# M452x2015.net
KiCad netlist of a schematic drawn in EAGLE
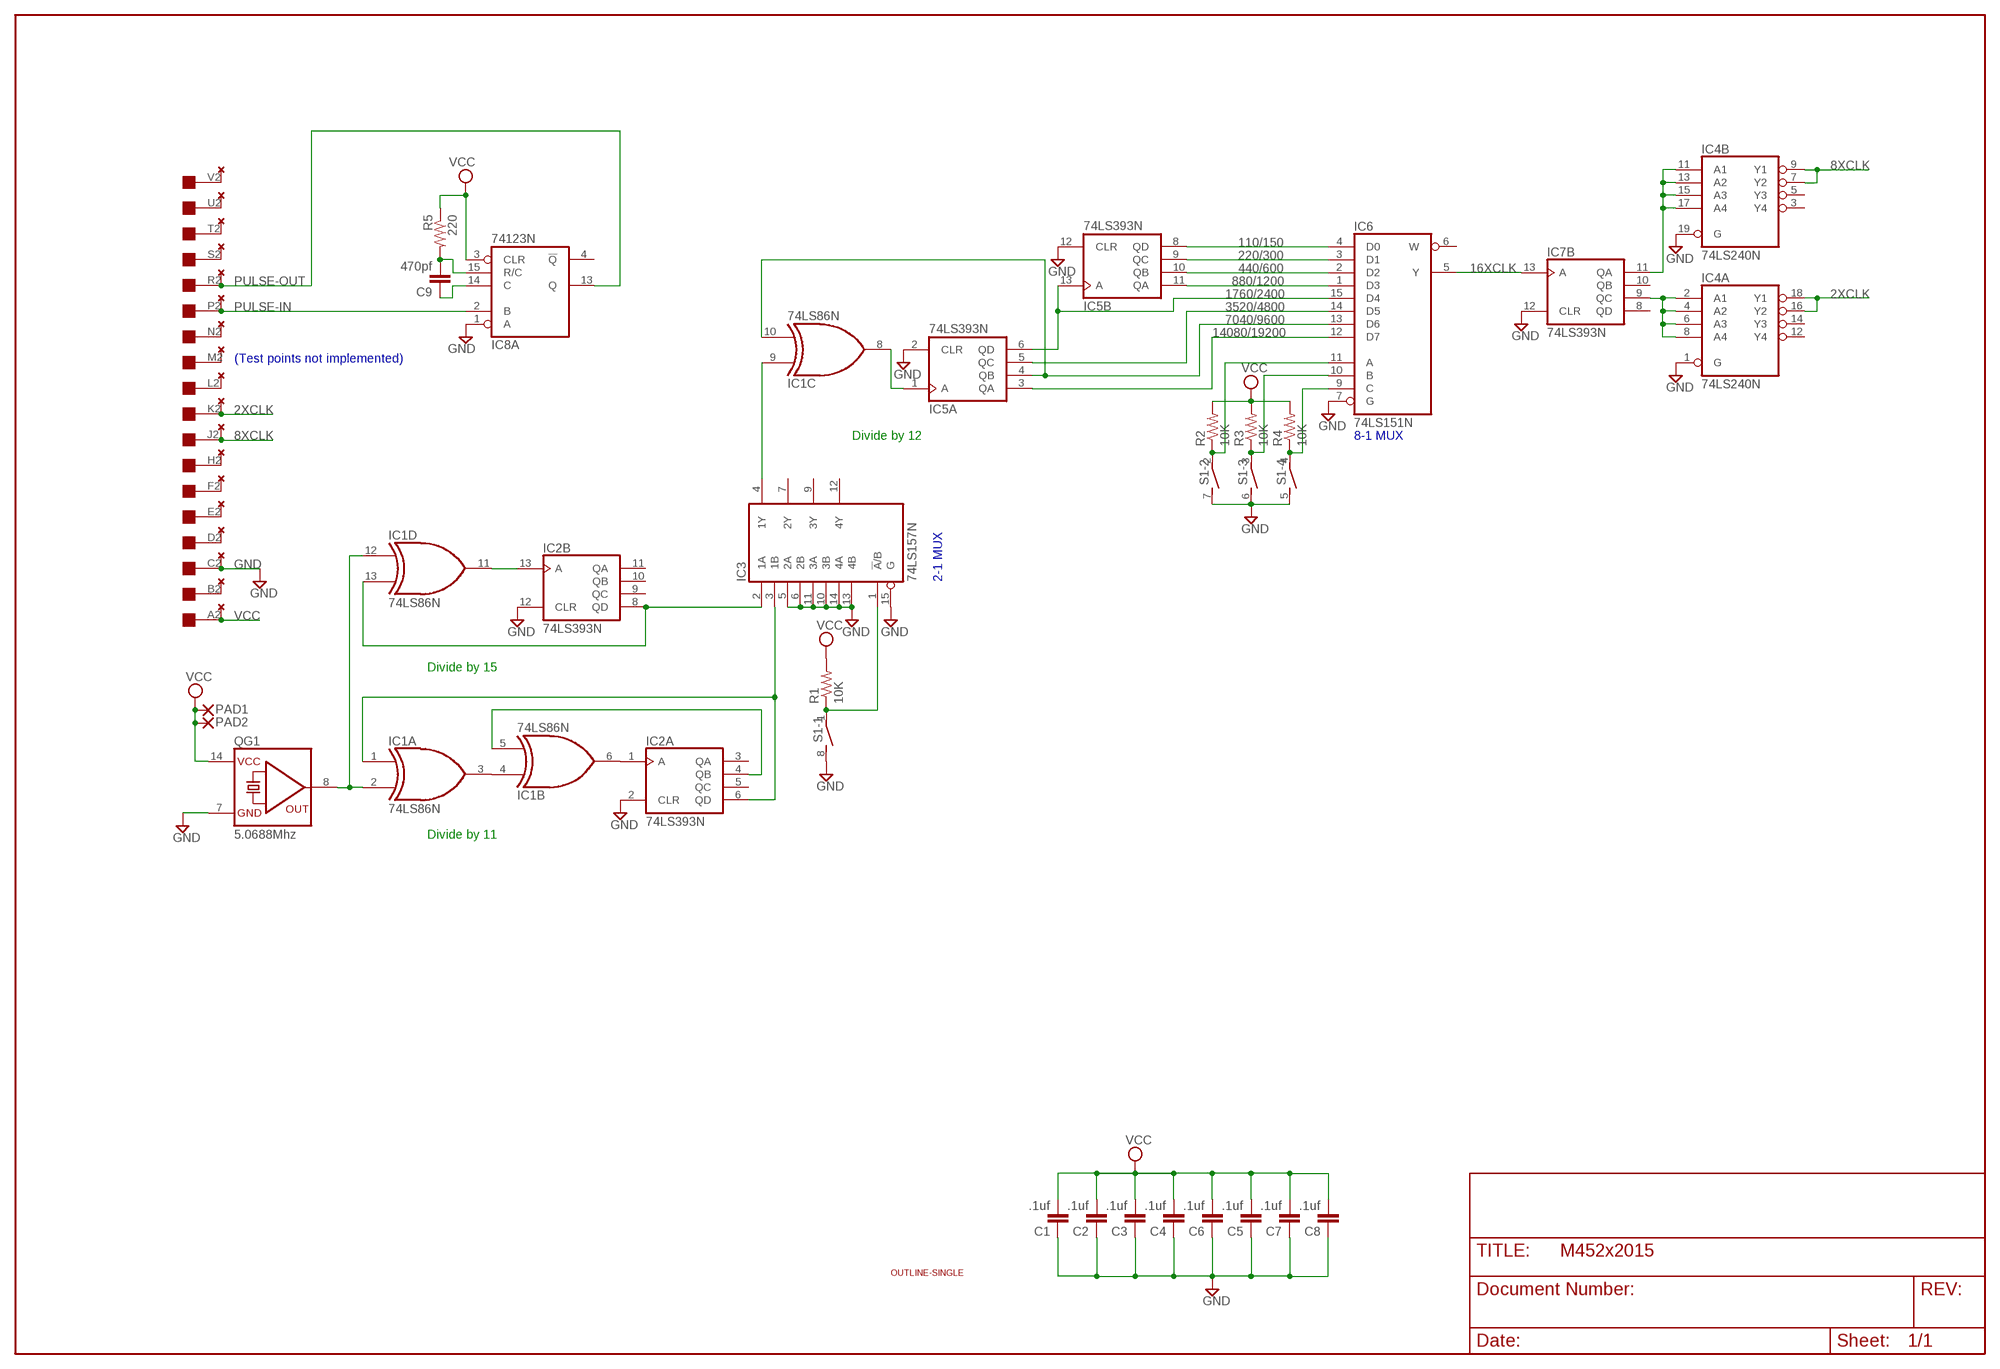
[diagram p0: schematic, sheet 1]

(export (version "E")
  (design (tool "Eeschema 10.0.6"))
  (components
    (comp (ref "C1")
      (value ".1uf")
      (footprint "eagle-import:C050-025X075")
      (libsource (lib "eagle-import") (part "C-EU050-025X075"))
    )
    (comp (ref "C2")
      (value ".1uf")
      (footprint "eagle-import:C050-025X075")
      (libsource (lib "eagle-import") (part "C-EU050-025X075"))
    )
    (comp (ref "C3")
      (value ".1uf")
      (footprint "eagle-import:C050-025X075")
      (libsource (lib "eagle-import") (part "C-EU050-025X075"))
    )
    (comp (ref "C4")
      (value ".1uf")
      (footprint "eagle-import:C050-025X075")
      (libsource (lib "eagle-import") (part "C-EU050-025X075"))
    )
    (comp (ref "C5")
      (value ".1uf")
      (footprint "eagle-import:C050-025X075")
      (libsource (lib "eagle-import") (part "C-EU050-025X075"))
    )
    (comp (ref "C6")
      (value ".1uf")
      (footprint "eagle-import:C050-025X075")
      (libsource (lib "eagle-import") (part "C-EU050-025X075"))
    )
    (comp (ref "C7")
      (value ".1uf")
      (footprint "eagle-import:C050-025X075")
      (libsource (lib "eagle-import") (part "C-EU050-025X075"))
    )
    (comp (ref "C8")
      (value ".1uf")
      (footprint "eagle-import:C050-025X075")
      (libsource (lib "eagle-import") (part "C-EU050-025X075"))
    )
    (comp (ref "C9")
      (value "470pf")
      (footprint "eagle-import:C050-025X075")
      (libsource (lib "eagle-import") (part "C-EU050-025X075"))
    )
    (comp (ref "IC1")
      (value "74LS86N")
      (footprint "eagle-import:DIL14")
      (libsource (lib "eagle-import") (part "7486NLS"))
    )
    (comp (ref "IC2")
      (value "74LS393N")
      (footprint "eagle-import:DIL14")
      (libsource (lib "eagle-import") (part "74393NLS"))
    )
    (comp (ref "IC3")
      (value "74LS157N")
      (footprint "eagle-import:DIL16")
      (libsource (lib "eagle-import") (part "74157NLS"))
    )
    (comp (ref "IC4")
      (value "74LS240N")
      (footprint "eagle-import:DIL20")
      (libsource (lib "eagle-import") (part "74240NLS"))
    )
    (comp (ref "IC5")
      (value "74LS393N")
      (footprint "eagle-import:DIL14")
      (libsource (lib "eagle-import") (part "74393NLS"))
    )
    (comp (ref "IC6")
      (value "74LS151N")
      (footprint "eagle-import:DIL16")
      (libsource (lib "eagle-import") (part "74151N"))
    )
    (comp (ref "IC7")
      (value "74LS393N")
      (footprint "eagle-import:DIL14")
      (libsource (lib "eagle-import") (part "74393NLS"))
    )
    (comp (ref "IC8")
      (value "74123N")
      (footprint "eagle-import:DIL16")
      (libsource (lib "eagle-import") (part "74123N"))
    )
    (comp (ref "PAD1")
      (value "1,6/0,8")
      (footprint "eagle-import:1,6_0,8")
      (libsource (lib "eagle-import") (part "1,6/0,8"))
    )
    (comp (ref "PAD2")
      (value "1,6/0,8")
      (footprint "eagle-import:1,6_0,8")
      (libsource (lib "eagle-import") (part "1,6/0,8"))
    )
    (comp (ref "QG1")
      (value "5.0688Mhz")
      (footprint "eagle-import:DIL14S")
      (libsource (lib "eagle-import") (part "QG5860"))
    )
    (comp (ref "R1")
      (value "10K")
      (footprint "eagle-import:0204_7")
      (libsource (lib "eagle-import") (part "R-US_0204/7"))
    )
    (comp (ref "R2")
      (value "10K")
      (footprint "eagle-import:0204_7")
      (libsource (lib "eagle-import") (part "R-US_0204/7"))
    )
    (comp (ref "R3")
      (value "10K")
      (footprint "eagle-import:0204_7")
      (libsource (lib "eagle-import") (part "R-US_0204/7"))
    )
    (comp (ref "R4")
      (value "10K")
      (footprint "eagle-import:0204_7")
      (libsource (lib "eagle-import") (part "R-US_0204/7"))
    )
    (comp (ref "R5")
      (value "220")
      (footprint "eagle-import:0204_7")
      (libsource (lib "eagle-import") (part "R-US_0204/7"))
    )
    (comp (ref "S1")
      (value "DIP04S")
      (footprint "eagle-import:DIP04S")
      (libsource (lib "eagle-import") (part "DIP04S"))
    )
    (comp (ref "U$1")
      (value "OUTLINE-SINGLE")
      (footprint "eagle-import:SINGLE")
      (libsource (lib "eagle-import") (part "OUTLINE-SINGLE"))
    )
    (comp (ref "U$2")
      (value "EDGE-1")
      (footprint "eagle-import:EDGE-CON1")
      (libsource (lib "eagle-import") (part "EDGE-1"))
    )
    (comp (ref "U$3")
      (value "THRU-HOLE1")
      (footprint "eagle-import:THRU-HOLE1")
      (libsource (lib "eagle-import") (part "THRU-HOLE1"))
    )
  )
  (nets
    (net (code "1") (name "/2XCLK") (class "Default")
      (node (ref "IC4") (pin "16") (pinfunction "Y2_16") (pintype "tri_state"))
      (node (ref "IC4") (pin "18") (pinfunction "Y1_18") (pintype "tri_state"))
      (node (ref "U$2") (pin "K2") (pinfunction "1_K2") (pintype "bidirectional"))
      (node (ref "U$3") (pin "K2") (pinfunction "P$1_K2") (pintype "passive"))
    )
    (net (code "2") (name "/8XCLK") (class "Default")
      (node (ref "IC4") (pin "7") (pinfunction "Y2_7") (pintype "tri_state"))
      (node (ref "IC4") (pin "9") (pinfunction "Y1_9") (pintype "tri_state"))
      (node (ref "U$2") (pin "J2") (pinfunction "1_J2") (pintype "bidirectional"))
      (node (ref "U$3") (pin "J2") (pinfunction "P$1_J2") (pintype "passive"))
    )
    (net (code "3") (name "/16XCLK") (class "Default")
      (node (ref "IC6") (pin "5") (pinfunction "Y_5") (pintype "output"))
      (node (ref "IC7") (pin "13") (pinfunction "A_13") (pintype "input"))
    )
    (net (code "4") (name "/110{slash}150") (class "Default")
      (node (ref "IC5") (pin "8") (pinfunction "QD_8") (pintype "output"))
      (node (ref "IC6") (pin "4") (pinfunction "D0_4") (pintype "input"))
    )
    (net (code "5") (name "/220{slash}300") (class "Default")
      (node (ref "IC5") (pin "9") (pinfunction "QC_9") (pintype "output"))
      (node (ref "IC6") (pin "3") (pinfunction "D1_3") (pintype "input"))
    )
    (net (code "6") (name "/440{slash}600") (class "Default")
      (node (ref "IC5") (pin "10") (pinfunction "QB_10") (pintype "output"))
      (node (ref "IC6") (pin "2") (pinfunction "D2_2") (pintype "input"))
    )
    (net (code "7") (name "/880{slash}1200") (class "Default")
      (node (ref "IC5") (pin "11") (pinfunction "QA_11") (pintype "output"))
      (node (ref "IC6") (pin "1") (pinfunction "D3_1") (pintype "input"))
    )
    (net (code "8") (name "/1760{slash}2400") (class "Default")
      (node (ref "IC5") (pin "13") (pinfunction "A_13") (pintype "input"))
      (node (ref "IC5") (pin "6") (pinfunction "QD_6") (pintype "output"))
      (node (ref "IC6") (pin "15") (pinfunction "D4_15") (pintype "input"))
    )
    (net (code "9") (name "/3520{slash}4800") (class "Default")
      (node (ref "IC5") (pin "5") (pinfunction "QC_5") (pintype "output"))
      (node (ref "IC6") (pin "14") (pinfunction "D5_14") (pintype "input"))
    )
    (net (code "10") (name "/7040{slash}9600") (class "Default")
      (node (ref "IC1") (pin "10") (pinfunction "I1_10") (pintype "input"))
      (node (ref "IC5") (pin "4") (pinfunction "QB_4") (pintype "output"))
      (node (ref "IC6") (pin "13") (pinfunction "D6_13") (pintype "input"))
    )
    (net (code "11") (name "/14080{slash}19200") (class "Default")
      (node (ref "IC5") (pin "3") (pinfunction "QA_3") (pintype "output"))
      (node (ref "IC6") (pin "12") (pinfunction "D7_12") (pintype "input"))
    )
    (net (code "12") (name "/PULSE-IN") (class "Default")
      (node (ref "IC8") (pin "2") (pinfunction "B_2") (pintype "input"))
      (node (ref "U$2") (pin "P2") (pinfunction "1_P2") (pintype "bidirectional"))
      (node (ref "U$3") (pin "P2") (pinfunction "P$1_P2") (pintype "passive"))
    )
    (net (code "13") (name "/PULSE-OUT") (class "Default")
      (node (ref "IC8") (pin "13") (pinfunction "Q_13") (pintype "output"))
      (node (ref "U$2") (pin "R2") (pinfunction "1_R2") (pintype "bidirectional"))
      (node (ref "U$3") (pin "R2") (pinfunction "P$1_R2") (pintype "passive"))
    )
    (net (code "14") (name "GND") (class "Default")
      (node (ref "C1") (pin "1") (pinfunction "1_1") (pintype "passive"))
      (node (ref "C2") (pin "1") (pinfunction "1_1") (pintype "passive"))
      (node (ref "C3") (pin "1") (pinfunction "1_1") (pintype "passive"))
      (node (ref "C4") (pin "1") (pinfunction "1_1") (pintype "passive"))
      (node (ref "C5") (pin "1") (pinfunction "1_1") (pintype "passive"))
      (node (ref "C6") (pin "1") (pinfunction "1_1") (pintype "passive"))
      (node (ref "C7") (pin "1") (pinfunction "1_1") (pintype "passive"))
      (node (ref "C8") (pin "1") (pinfunction "1_1") (pintype "passive"))
      (node (ref "IC2") (pin "12") (pinfunction "CLR_12") (pintype "input"))
      (node (ref "IC2") (pin "2") (pinfunction "CLR_2") (pintype "input"))
      (node (ref "IC3") (pin "10") (pinfunction "3B_10") (pintype "input"))
      (node (ref "IC3") (pin "11") (pinfunction "3A_11") (pintype "input"))
      (node (ref "IC3") (pin "13") (pinfunction "4B_13") (pintype "input"))
      (node (ref "IC3") (pin "14") (pinfunction "4A_14") (pintype "input"))
      (node (ref "IC3") (pin "15") (pinfunction "G_15") (pintype "input"))
      (node (ref "IC3") (pin "5") (pinfunction "2A_5") (pintype "input"))
      (node (ref "IC3") (pin "6") (pinfunction "2B_6") (pintype "input"))
      (node (ref "IC4") (pin "1") (pinfunction "G_1") (pintype "input"))
      (node (ref "IC4") (pin "19") (pinfunction "G_19") (pintype "input"))
      (node (ref "IC5") (pin "12") (pinfunction "CLR_12") (pintype "input"))
      (node (ref "IC5") (pin "2") (pinfunction "CLR_2") (pintype "input"))
      (node (ref "IC6") (pin "7") (pinfunction "G_7") (pintype "input"))
      (node (ref "IC7") (pin "12") (pinfunction "CLR_12") (pintype "input"))
      (node (ref "IC8") (pin "1") (pinfunction "A_1") (pintype "input"))
      (node (ref "QG1") (pin "7") (pinfunction "GND_7") (pintype "power_in"))
      (node (ref "S1") (pin "5") (pinfunction "2_5") (pintype "passive"))
      (node (ref "S1") (pin "6") (pinfunction "2_6") (pintype "passive"))
      (node (ref "S1") (pin "7") (pinfunction "2_7") (pintype "passive"))
      (node (ref "S1") (pin "8") (pinfunction "2_8") (pintype "passive"))
      (node (ref "U$2") (pin "C2") (pinfunction "1_C2") (pintype "bidirectional"))
      (node (ref "U$3") (pin "C2") (pinfunction "P$1_C2") (pintype "passive"))
    )
    (net (code "15") (name "Net-(IC1A-I0)") (class "Default")
      (node (ref "IC1") (pin "1") (pinfunction "I0_1") (pintype "input"))
      (node (ref "IC2") (pin "6") (pinfunction "QD_6") (pintype "output"))
      (node (ref "IC3") (pin "3") (pinfunction "1B_3") (pintype "input"))
    )
    (net (code "16") (name "Net-(IC1A-I1)") (class "Default")
      (node (ref "IC1") (pin "12") (pinfunction "I0_12") (pintype "input"))
      (node (ref "IC1") (pin "2") (pinfunction "I1_2") (pintype "input"))
      (node (ref "QG1") (pin "8") (pinfunction "OUT_8") (pintype "output"))
    )
    (net (code "17") (name "Net-(IC1A-O)") (class "Default")
      (node (ref "IC1") (pin "3") (pinfunction "O_3") (pintype "output"))
      (node (ref "IC1") (pin "4") (pinfunction "I0_4") (pintype "input"))
    )
    (net (code "18") (name "Net-(IC1B-I1)") (class "Default")
      (node (ref "IC1") (pin "5") (pinfunction "I1_5") (pintype "input"))
      (node (ref "IC2") (pin "4") (pinfunction "QB_4") (pintype "output"))
    )
    (net (code "19") (name "Net-(IC1B-O)") (class "Default")
      (node (ref "IC1") (pin "6") (pinfunction "O_6") (pintype "output"))
      (node (ref "IC2") (pin "1") (pinfunction "A_1") (pintype "input"))
    )
    (net (code "20") (name "Net-(IC1C-I0)") (class "Default")
      (node (ref "IC1") (pin "9") (pinfunction "I0_9") (pintype "input"))
      (node (ref "IC3") (pin "4") (pinfunction "1Y_4") (pintype "output"))
    )
    (net (code "21") (name "Net-(IC1C-O)") (class "Default")
      (node (ref "IC1") (pin "8") (pinfunction "O_8") (pintype "output"))
      (node (ref "IC5") (pin "1") (pinfunction "A_1") (pintype "input"))
    )
    (net (code "22") (name "Net-(IC1D-I1)") (class "Default")
      (node (ref "IC1") (pin "13") (pinfunction "I1_13") (pintype "input"))
      (node (ref "IC2") (pin "8") (pinfunction "QD_8") (pintype "output"))
      (node (ref "IC3") (pin "2") (pinfunction "1A_2") (pintype "input"))
    )
    (net (code "23") (name "Net-(IC1D-O)") (class "Default")
      (node (ref "IC1") (pin "11") (pinfunction "O_11") (pintype "output"))
      (node (ref "IC2") (pin "13") (pinfunction "A_13") (pintype "input"))
    )
    (net (code "24") (name "Net-(IC3A-~{A}{slash}B)") (class "Default")
      (node (ref "IC3") (pin "1") (pinfunction "~{A}/B_1") (pintype "input"))
      (node (ref "R1") (pin "1") (pinfunction "1_1") (pintype "passive"))
      (node (ref "S1") (pin "1") (pinfunction "1_1") (pintype "passive"))
    )
    (net (code "25") (name "Net-(IC4A-A1)") (class "Default")
      (node (ref "IC4") (pin "2") (pinfunction "A1_2") (pintype "input"))
      (node (ref "IC4") (pin "4") (pinfunction "A2_4") (pintype "input"))
      (node (ref "IC4") (pin "6") (pinfunction "A3_6") (pintype "input"))
      (node (ref "IC4") (pin "8") (pinfunction "A4_8") (pintype "input"))
      (node (ref "IC7") (pin "9") (pinfunction "QC_9") (pintype "output"))
    )
    (net (code "26") (name "Net-(IC4B-A1)") (class "Default")
      (node (ref "IC4") (pin "11") (pinfunction "A1_11") (pintype "input"))
      (node (ref "IC4") (pin "13") (pinfunction "A2_13") (pintype "input"))
      (node (ref "IC4") (pin "15") (pinfunction "A3_15") (pintype "input"))
      (node (ref "IC4") (pin "17") (pinfunction "A4_17") (pintype "input"))
      (node (ref "IC7") (pin "11") (pinfunction "QA_11") (pintype "output"))
    )
    (net (code "27") (name "Net-(IC6A-A)") (class "Default")
      (node (ref "IC6") (pin "11") (pinfunction "A_11") (pintype "input"))
      (node (ref "R2") (pin "1") (pinfunction "1_1") (pintype "passive"))
      (node (ref "S1") (pin "2") (pinfunction "1_2") (pintype "passive"))
    )
    (net (code "28") (name "Net-(IC6A-B)") (class "Default")
      (node (ref "IC6") (pin "10") (pinfunction "B_10") (pintype "input"))
      (node (ref "R3") (pin "1") (pinfunction "1_1") (pintype "passive"))
      (node (ref "S1") (pin "3") (pinfunction "1_3") (pintype "passive"))
    )
    (net (code "29") (name "Net-(IC6A-C)") (class "Default")
      (node (ref "IC6") (pin "9") (pinfunction "C_9") (pintype "input"))
      (node (ref "R4") (pin "1") (pinfunction "1_1") (pintype "passive"))
      (node (ref "S1") (pin "4") (pinfunction "1_4") (pintype "passive"))
    )
    (net (code "30") (name "Net-(IC8A-C)") (class "Default")
      (node (ref "C9") (pin "1") (pinfunction "1_1") (pintype "passive"))
      (node (ref "IC8") (pin "14") (pinfunction "C_14") (pintype "input"))
    )
    (net (code "31") (name "Net-(IC8A-R{slash}C)") (class "Default")
      (node (ref "C9") (pin "2") (pinfunction "2_2") (pintype "passive"))
      (node (ref "IC8") (pin "15") (pinfunction "R/C_15") (pintype "input"))
      (node (ref "R5") (pin "2") (pinfunction "2_2") (pintype "passive"))
    )
    (net (code "32") (name "Net-(U$2B-1)") (class "Default")
      (node (ref "U$2") (pin "B2") (pinfunction "1_B2") (pintype "bidirectional"))
      (node (ref "U$3") (pin "B2") (pinfunction "P$1_B2") (pintype "passive"))
    )
    (net (code "33") (name "Net-(U$2D-1)") (class "Default")
      (node (ref "U$2") (pin "D2") (pinfunction "1_D2") (pintype "bidirectional"))
      (node (ref "U$3") (pin "D2") (pinfunction "P$1_D2") (pintype "passive"))
    )
    (net (code "34") (name "Net-(U$2E-1)") (class "Default")
      (node (ref "U$2") (pin "E2") (pinfunction "1_E2") (pintype "bidirectional"))
      (node (ref "U$3") (pin "E2") (pinfunction "P$1_E2") (pintype "passive"))
    )
    (net (code "35") (name "Net-(U$2F-1)") (class "Default")
      (node (ref "U$2") (pin "F2") (pinfunction "1_F2") (pintype "bidirectional"))
      (node (ref "U$3") (pin "F2") (pinfunction "P$1_F2") (pintype "passive"))
    )
    (net (code "36") (name "Net-(U$2G-1)") (class "Default")
      (node (ref "U$2") (pin "H2") (pinfunction "1_H2") (pintype "bidirectional"))
      (node (ref "U$3") (pin "H2") (pinfunction "P$1_H2") (pintype "passive"))
    )
    (net (code "37") (name "Net-(U$2J-1)") (class "Default")
      (node (ref "U$2") (pin "L2") (pinfunction "1_L2") (pintype "bidirectional"))
      (node (ref "U$3") (pin "L2") (pinfunction "P$1_L2") (pintype "passive"))
    )
    (net (code "38") (name "Net-(U$2K-1)") (class "Default")
      (node (ref "U$2") (pin "M2") (pinfunction "1_M2") (pintype "bidirectional"))
      (node (ref "U$3") (pin "M2") (pinfunction "P$1_M2") (pintype "passive"))
    )
    (net (code "39") (name "Net-(U$2L-1)") (class "Default")
      (node (ref "U$2") (pin "N2") (pinfunction "1_N2") (pintype "bidirectional"))
      (node (ref "U$3") (pin "N2") (pinfunction "P$1_N2") (pintype "passive"))
    )
    (net (code "40") (name "Net-(U$2O-1)") (class "Default")
      (node (ref "U$2") (pin "S2") (pinfunction "1_S2") (pintype "bidirectional"))
      (node (ref "U$3") (pin "S2") (pinfunction "P$1_S2") (pintype "passive"))
    )
    (net (code "41") (name "Net-(U$2P-1)") (class "Default")
      (node (ref "U$2") (pin "T2") (pinfunction "1_T2") (pintype "bidirectional"))
      (node (ref "U$3") (pin "T2") (pinfunction "P$1_T2") (pintype "passive"))
    )
    (net (code "42") (name "Net-(U$2Q-1)") (class "Default")
      (node (ref "U$2") (pin "U2") (pinfunction "1_U2") (pintype "bidirectional"))
      (node (ref "U$3") (pin "U2") (pinfunction "P$1_U2") (pintype "passive"))
    )
    (net (code "43") (name "Net-(U$2R-1)") (class "Default")
      (node (ref "U$2") (pin "V2") (pinfunction "1_V2") (pintype "bidirectional"))
      (node (ref "U$3") (pin "V2") (pinfunction "P$1_V2") (pintype "passive"))
    )
    (net (code "44") (name "VCC") (class "Default")
      (node (ref "C1") (pin "2") (pinfunction "2_2") (pintype "passive"))
      (node (ref "C2") (pin "2") (pinfunction "2_2") (pintype "passive"))
      (node (ref "C3") (pin "2") (pinfunction "2_2") (pintype "passive"))
      (node (ref "C4") (pin "2") (pinfunction "2_2") (pintype "passive"))
      (node (ref "C5") (pin "2") (pinfunction "2_2") (pintype "passive"))
      (node (ref "C6") (pin "2") (pinfunction "2_2") (pintype "passive"))
      (node (ref "C7") (pin "2") (pinfunction "2_2") (pintype "passive"))
      (node (ref "C8") (pin "2") (pinfunction "2_2") (pintype "passive"))
      (node (ref "IC8") (pin "3") (pinfunction "CLR_3") (pintype "input"))
      (node (ref "PAD1") (pin "1") (pinfunction "P_1") (pintype "passive"))
      (node (ref "PAD2") (pin "1") (pinfunction "P_1") (pintype "passive"))
      (node (ref "QG1") (pin "14") (pinfunction "VCC_14") (pintype "power_in"))
      (node (ref "R1") (pin "2") (pinfunction "2_2") (pintype "passive"))
      (node (ref "R2") (pin "2") (pinfunction "2_2") (pintype "passive"))
      (node (ref "R3") (pin "2") (pinfunction "2_2") (pintype "passive"))
      (node (ref "R4") (pin "2") (pinfunction "2_2") (pintype "passive"))
      (node (ref "R5") (pin "1") (pinfunction "1_1") (pintype "passive"))
      (node (ref "U$2") (pin "A2") (pinfunction "1_A2") (pintype "bidirectional"))
      (node (ref "U$3") (pin "A2") (pinfunction "P$1_A2") (pintype "passive"))
    )
    (net (code "45") (name "unconnected-(IC2A-QA-Pad3)") (class "Default")
      (node (ref "IC2") (pin "3") (pinfunction "QA_3") (pintype "output"))
    )
    (net (code "46") (name "unconnected-(IC2A-QC-Pad5)") (class "Default")
      (node (ref "IC2") (pin "5") (pinfunction "QC_5") (pintype "output"))
    )
    (net (code "47") (name "unconnected-(IC2B-QA-Pad11)") (class "Default")
      (node (ref "IC2") (pin "11") (pinfunction "QA_11") (pintype "output"))
    )
    (net (code "48") (name "unconnected-(IC2B-QB-Pad10)") (class "Default")
      (node (ref "IC2") (pin "10") (pinfunction "QB_10") (pintype "output"))
    )
    (net (code "49") (name "unconnected-(IC2B-QC-Pad9)") (class "Default")
      (node (ref "IC2") (pin "9") (pinfunction "QC_9") (pintype "output"))
    )
    (net (code "50") (name "unconnected-(IC3A-2Y-Pad7)") (class "Default")
      (node (ref "IC3") (pin "7") (pinfunction "2Y_7") (pintype "output"))
    )
    (net (code "51") (name "unconnected-(IC3A-3Y-Pad9)") (class "Default")
      (node (ref "IC3") (pin "9") (pinfunction "3Y_9") (pintype "output"))
    )
    (net (code "52") (name "unconnected-(IC3A-4Y-Pad12)") (class "Default")
      (node (ref "IC3") (pin "12") (pinfunction "4Y_12") (pintype "output"))
    )
    (net (code "53") (name "unconnected-(IC4A-Y3-Pad14)") (class "Default")
      (node (ref "IC4") (pin "14") (pinfunction "Y3_14") (pintype "tri_state"))
    )
    (net (code "54") (name "unconnected-(IC4A-Y4-Pad12)") (class "Default")
      (node (ref "IC4") (pin "12") (pinfunction "Y4_12") (pintype "tri_state"))
    )
    (net (code "55") (name "unconnected-(IC4B-Y3-Pad5)") (class "Default")
      (node (ref "IC4") (pin "5") (pinfunction "Y3_5") (pintype "tri_state"))
    )
    (net (code "56") (name "unconnected-(IC4B-Y4-Pad3)") (class "Default")
      (node (ref "IC4") (pin "3") (pinfunction "Y4_3") (pintype "tri_state"))
    )
    (net (code "57") (name "unconnected-(IC6A-W-Pad6)") (class "Default")
      (node (ref "IC6") (pin "6") (pinfunction "W_6") (pintype "output"))
    )
    (net (code "58") (name "unconnected-(IC7B-QB-Pad10)") (class "Default")
      (node (ref "IC7") (pin "10") (pinfunction "QB_10") (pintype "output"))
    )
    (net (code "59") (name "unconnected-(IC7B-QD-Pad8)") (class "Default")
      (node (ref "IC7") (pin "8") (pinfunction "QD_8") (pintype "output"))
    )
    (net (code "60") (name "unconnected-(IC8A-~{Q}-Pad4)") (class "Default")
      (node (ref "IC8") (pin "4") (pinfunction "~{Q}_4") (pintype "output"))
    )
  )
)
